# Ethernet.net
KiCad netlist of a schematic drawn in Altium Designer
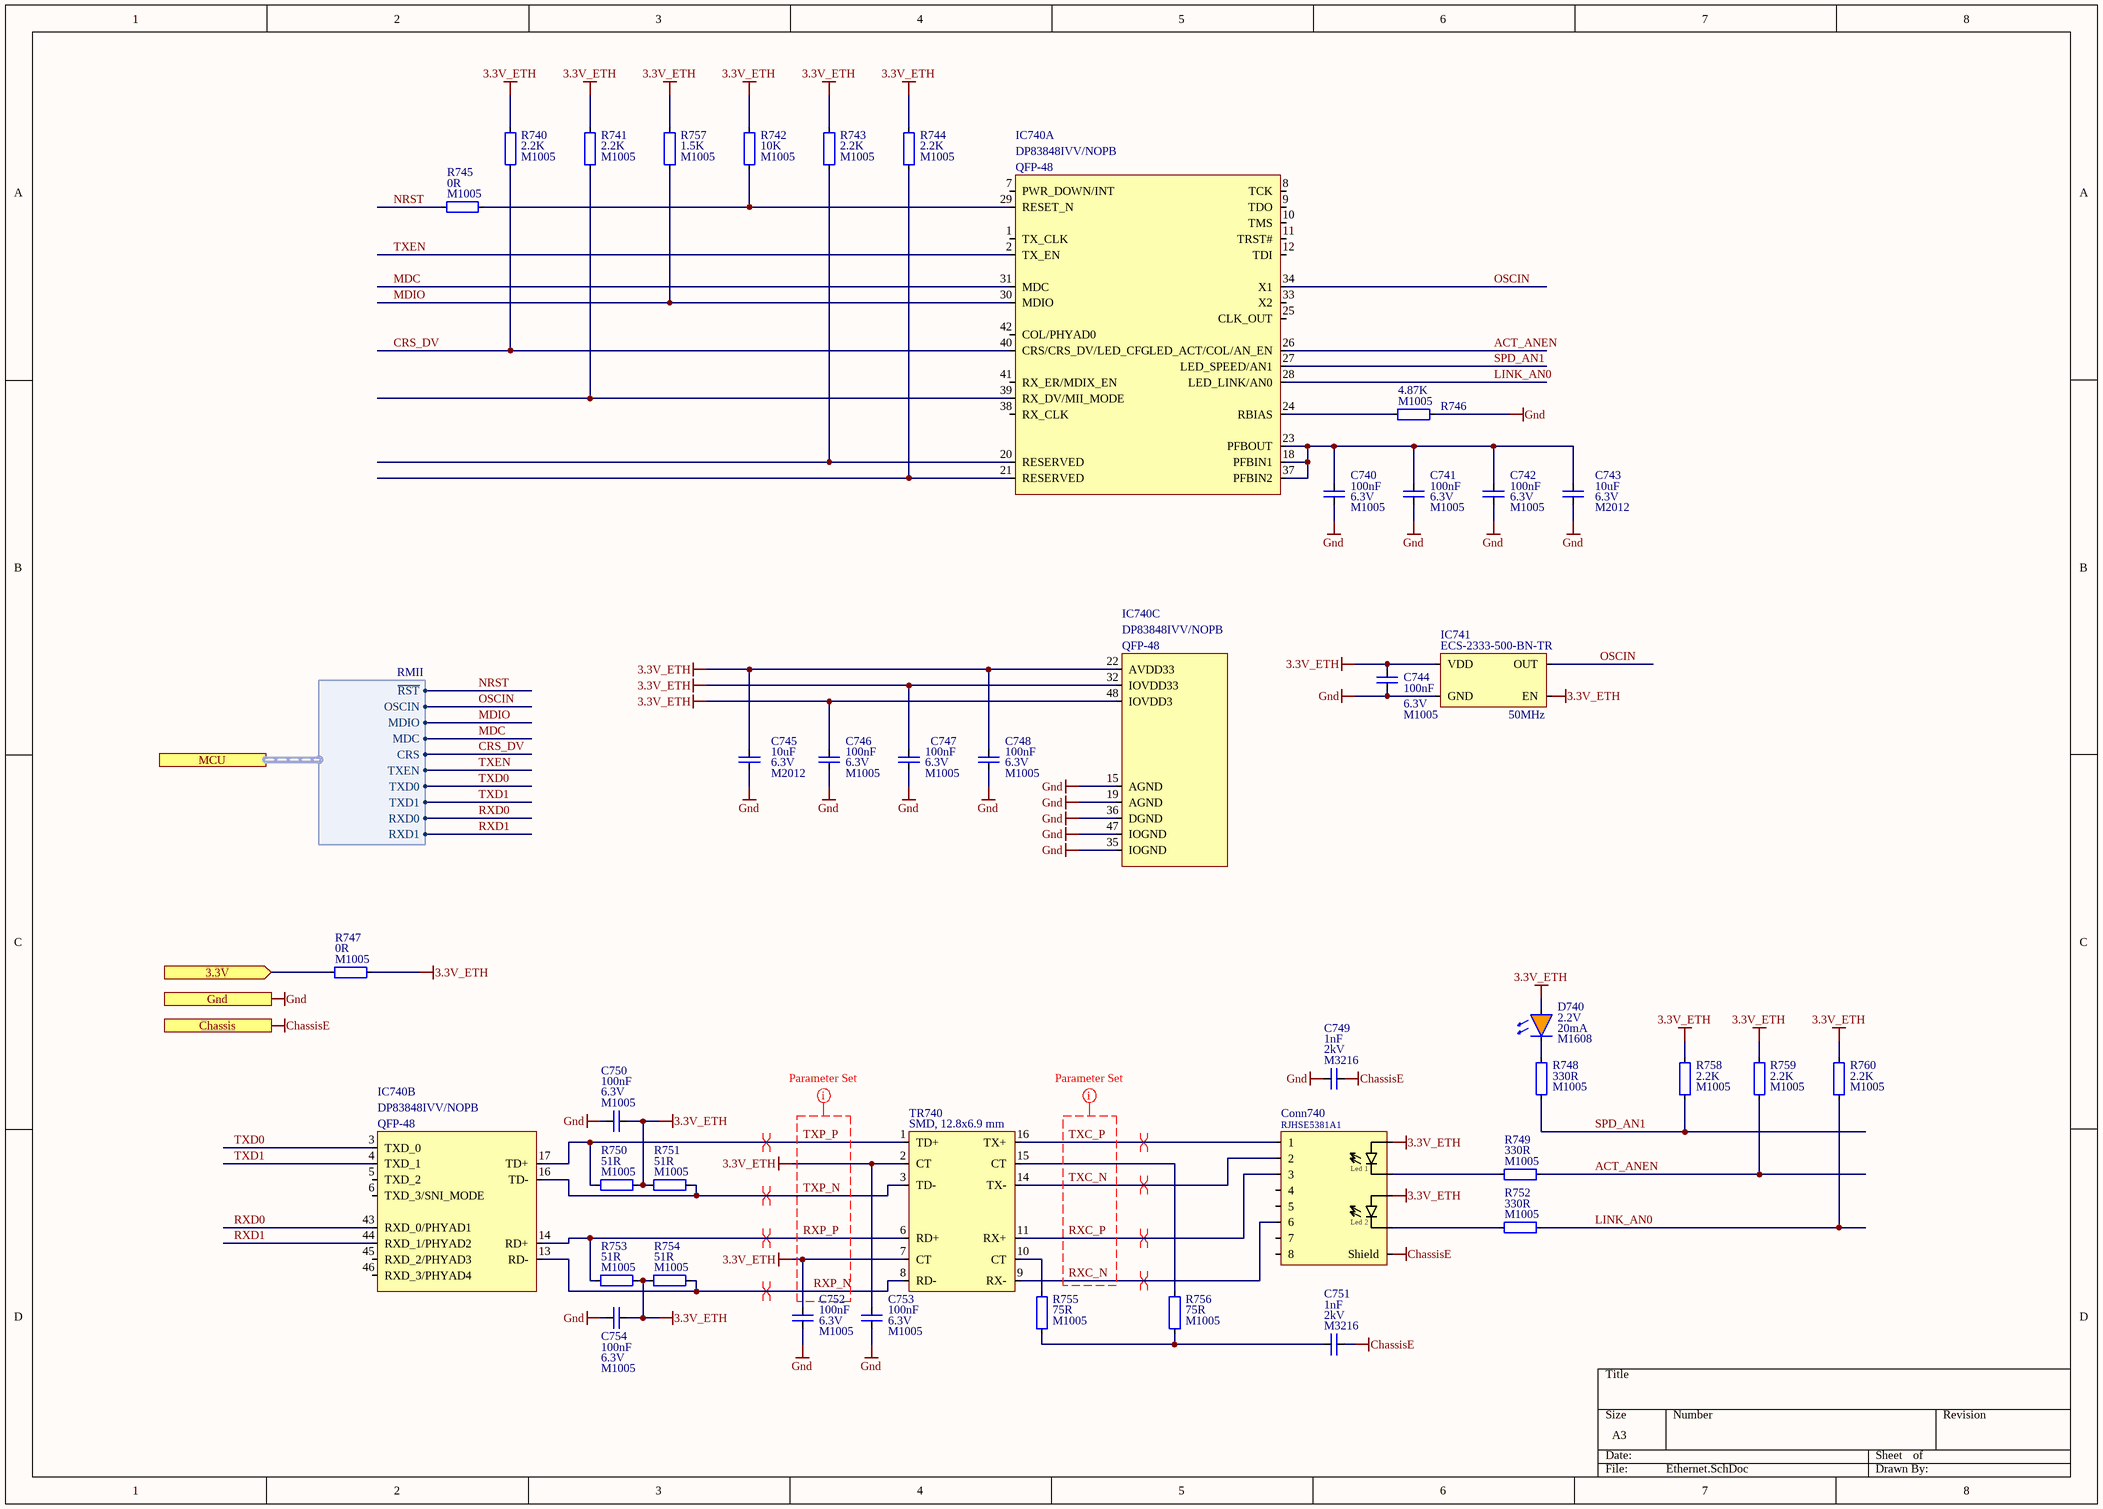
[diagram p0: Ethernet.SchDoc]

(export (version "E")
  (design (tool "Eeschema 10.0.6"))
  (components
    (comp (ref "C740")
      (value "100nF")
      (footprint "Capacitor_Ceramic_M1005_I0402")
      (description "Cap, Cer, 100nF, 6.3V, M1005")
      (fields
        (field (name "VOLTAGE") "6.3V")
        (field (name "MANUFACTURER PART NUMBER") "04026D104KAT4A")
        (field (name "MANUFACTURER") "Kyocera")
        (field (name "PACKAGE") "M1005")
      )
      (libsource (lib "Capacitor") (part "Capacitor_Ceramic"))
    )
    (comp (ref "C741")
      (value "100nF")
      (footprint "Capacitor_Ceramic_M1005_I0402")
      (description "Cap, Cer, 100nF, 6.3V, M1005")
      (fields
        (field (name "VOLTAGE") "6.3V")
        (field (name "MANUFACTURER PART NUMBER") "04026D104KAT4A")
        (field (name "MANUFACTURER") "Kyocera")
        (field (name "PACKAGE") "M1005")
      )
      (libsource (lib "Capacitor") (part "Capacitor_Ceramic"))
    )
    (comp (ref "C742")
      (value "100nF")
      (footprint "Capacitor_Ceramic_M1005_I0402")
      (description "Cap, Cer, 100nF, 6.3V, M1005")
      (fields
        (field (name "VOLTAGE") "6.3V")
        (field (name "MANUFACTURER PART NUMBER") "04026D104KAT4A")
        (field (name "MANUFACTURER") "Kyocera")
        (field (name "PACKAGE") "M1005")
      )
      (libsource (lib "Capacitor") (part "Capacitor_Ceramic"))
    )
    (comp (ref "C743")
      (value "10uF")
      (footprint "Capacitor_Ceramic_M2012_I0805")
      (description "Cap, Cer, 10uF, 6.3V, M2012")
      (fields
        (field (name "VOLTAGE") "6.3V")
        (field (name "MANUFACTURER PART NUMBER") "CL21A106MQFNNNE")
        (field (name "MANUFACTURER") "Samsung")
        (field (name "PACKAGE") "M2012")
      )
      (libsource (lib "Capacitor") (part "Capacitor_Ceramic"))
    )
    (comp (ref "C744")
      (value "100nF")
      (footprint "Capacitor_Ceramic_M1005_I0402")
      (description "Cap, Cer, 100nF, 6.3V, M1005")
      (fields
        (field (name "VOLTAGE") "6.3V")
        (field (name "MANUFACTURER PART NUMBER") "04026D104KAT4A")
        (field (name "MANUFACTURER") "Kyocera")
        (field (name "PACKAGE") "M1005")
      )
      (libsource (lib "Capacitor") (part "Capacitor_Ceramic"))
    )
    (comp (ref "C745")
      (value "10uF")
      (footprint "Capacitor_Ceramic_M2012_I0805")
      (description "Cap, Cer, 10uF, 6.3V, M2012")
      (fields
        (field (name "VOLTAGE") "6.3V")
        (field (name "MANUFACTURER PART NUMBER") "CL21A106MQFNNNE")
        (field (name "MANUFACTURER") "Samsung")
        (field (name "PACKAGE") "M2012")
      )
      (libsource (lib "Capacitor") (part "Capacitor_Ceramic"))
    )
    (comp (ref "C746")
      (value "100nF")
      (footprint "Capacitor_Ceramic_M1005_I0402")
      (description "Cap, Cer, 100nF, 6.3V, M1005")
      (fields
        (field (name "VOLTAGE") "6.3V")
        (field (name "MANUFACTURER PART NUMBER") "04026D104KAT4A")
        (field (name "MANUFACTURER") "Kyocera")
        (field (name "PACKAGE") "M1005")
      )
      (libsource (lib "Capacitor") (part "Capacitor_Ceramic"))
    )
    (comp (ref "C747")
      (value "100nF")
      (footprint "Capacitor_Ceramic_M1005_I0402")
      (description "Cap, Cer, 100nF, 6.3V, M1005")
      (fields
        (field (name "VOLTAGE") "6.3V")
        (field (name "MANUFACTURER PART NUMBER") "04026D104KAT4A")
        (field (name "MANUFACTURER") "Kyocera")
        (field (name "PACKAGE") "M1005")
      )
      (libsource (lib "Capacitor") (part "Capacitor_Ceramic"))
    )
    (comp (ref "C748")
      (value "100nF")
      (footprint "Capacitor_Ceramic_M1005_I0402")
      (description "Cap, Cer, 100nF, 6.3V, M1005")
      (fields
        (field (name "VOLTAGE") "6.3V")
        (field (name "MANUFACTURER PART NUMBER") "04026D104KAT4A")
        (field (name "MANUFACTURER") "Kyocera")
        (field (name "PACKAGE") "M1005")
      )
      (libsource (lib "Capacitor") (part "Capacitor_Ceramic"))
    )
    (comp (ref "C749")
      (value "1nF")
      (footprint "Capacitor_Ceramic_M3216_I1206")
      (description "Cap, Cer, 1nF, 2kV, M3216")
      (fields
        (field (name "VOLTAGE") "2kV")
        (field (name "MANUFACTURER PART NUMBER") "CC1206MKX7RDBB102")
        (field (name "MANUFACTURER") "Yageo")
        (field (name "PACKAGE") "M3216")
      )
      (libsource (lib "Capacitor") (part "Capacitor_Ceramic"))
    )
    (comp (ref "C750")
      (value "100nF")
      (footprint "Capacitor_Ceramic_M1005_I0402")
      (description "Cap, Cer, 100nF, 6.3V, M1005")
      (fields
        (field (name "VOLTAGE") "6.3V")
        (field (name "MANUFACTURER PART NUMBER") "04026D104KAT4A")
        (field (name "MANUFACTURER") "Kyocera")
        (field (name "PACKAGE") "M1005")
      )
      (libsource (lib "Capacitor") (part "Capacitor_Ceramic"))
    )
    (comp (ref "C751")
      (value "1nF")
      (footprint "Capacitor_Ceramic_M3216_I1206")
      (description "Cap, Cer, 1nF, 2kV, M3216")
      (fields
        (field (name "VOLTAGE") "2kV")
        (field (name "MANUFACTURER PART NUMBER") "CC1206MKX7RDBB102")
        (field (name "MANUFACTURER") "Yageo")
        (field (name "PACKAGE") "M3216")
      )
      (libsource (lib "Capacitor") (part "Capacitor_Ceramic"))
    )
    (comp (ref "C752")
      (value "100nF")
      (footprint "Capacitor_Ceramic_M1005_I0402")
      (description "Cap, Cer, 100nF, 6.3V, M1005")
      (fields
        (field (name "VOLTAGE") "6.3V")
        (field (name "MANUFACTURER PART NUMBER") "04026D104KAT4A")
        (field (name "MANUFACTURER") "Kyocera")
        (field (name "PACKAGE") "M1005")
      )
      (libsource (lib "Capacitor") (part "Capacitor_Ceramic"))
    )
    (comp (ref "C753")
      (value "100nF")
      (footprint "Capacitor_Ceramic_M1005_I0402")
      (description "Cap, Cer, 100nF, 6.3V, M1005")
      (fields
        (field (name "VOLTAGE") "6.3V")
        (field (name "MANUFACTURER PART NUMBER") "04026D104KAT4A")
        (field (name "MANUFACTURER") "Kyocera")
        (field (name "PACKAGE") "M1005")
      )
      (libsource (lib "Capacitor") (part "Capacitor_Ceramic"))
    )
    (comp (ref "C754")
      (value "100nF")
      (footprint "Capacitor_Ceramic_M1005_I0402")
      (description "Cap, Cer, 100nF, 6.3V, M1005")
      (fields
        (field (name "VOLTAGE") "6.3V")
        (field (name "MANUFACTURER PART NUMBER") "04026D104KAT4A")
        (field (name "MANUFACTURER") "Kyocera")
        (field (name "PACKAGE") "M1005")
      )
      (libsource (lib "Capacitor") (part "Capacitor_Ceramic"))
    )
    (comp (ref "Conn740")
      (value "RJ45 - Amphenol, RJHSE-x38x-A1")
      (footprint "RJ45 - Amphenol, RJHSE-x38x-A1")
      (description "Conn, RJ45, 2 Leds, Shielded, Side Entry")
      (fields
        (field (name "MANUFACTURER") "Amphenol")
        (field (name "MANUFACTURER PART NUMBER") "RJHSE5381A1")
      )
      (libsource (lib "Connector - Registered Jack") (part "RJ45 - Amphenol, RJHSE-x38x-A1"))
    )
    (comp (ref "D740")
      (value "Diode_Led")
      (footprint "Diode_Smd_M1608_I0603_Orange1")
      (description "Diode, Led, Orange, 2.2V, 20mA, M1608")
      (fields
        (field (name "MANUFACTURER PART NUMBER") "SML-D12D1WT86")
        (field (name "MANUFACTURER") "Rohm")
        (field (name "CURRENT") "20mA")
        (field (name "VOLTAGE") "2.2V")
        (field (name "PACKAGE") "M1608")
      )
      (libsource (lib "Diode") (part "Diode_Led"))
    )
    (comp (ref "IC740")
      (value "Ethernet - Texas, DP83848xVV")
      (footprint "QFP-48, 7mm x 7mm, 0.5mm")
      (description "IC, Interface, Eth Phy, 10/100Mb, DP83848IVV")
      (fields
        (field (name "MANUFACTURER") "Texas")
        (field (name "MANUFACTURER PART NUMBER") "DP83848IVV/NOPB")
        (field (name "PACKAGE") "QFP-48")
      )
      (libsource (lib "IC - Interface") (part "Ethernet - Texas, DP83848xVV"))
    )
    (comp (ref "IC741")
      (value "Clock Oscillator - ECS, ECS-2325, ECS-2333")
      (footprint "Clock Oscillator - ECS, ECS-2325, ECS-2333")
      (description "IC, Oscillator, 50MHz")
      (fields
        (field (name "MANUFACTURER") "ECS")
        (field (name "FREQUENCY") "50MHz")
        (field (name "MANUFACTURER PART NUMBER") "ECS-2333-500-BN-TR")
      )
      (libsource (lib "IC - Clock, Timing, Oscillator") (part "Clock Oscillator - ECS, ECS-2325, ECS-2333"))
    )
    (comp (ref "R740")
      (value "2.2K")
      (footprint "Resistor_Smd_M1005_I0402")
      (description "Res, 2.2K, 1%, M1005")
      (fields
        (field (name "TOLERANCE") "1%")
        (field (name "MANUFACTURER") "Yageo")
        (field (name "PACKAGE") "M1005")
      )
      (libsource (lib "Resistor") (part "Resistor"))
    )
    (comp (ref "R741")
      (value "2.2K")
      (footprint "Resistor_Smd_M1005_I0402")
      (description "Res, 2.2K, 1%, M1005")
      (fields
        (field (name "TOLERANCE") "1%")
        (field (name "MANUFACTURER") "Yageo")
        (field (name "PACKAGE") "M1005")
      )
      (libsource (lib "Resistor") (part "Resistor"))
    )
    (comp (ref "R742")
      (value "10K")
      (footprint "Resistor_Smd_M1005_I0402")
      (description "Res, 10K, 1%, M1005")
      (fields
        (field (name "TOLERANCE") "1%")
        (field (name "MANUFACTURER") "Yageo")
        (field (name "PACKAGE") "M1005")
      )
      (libsource (lib "Resistor") (part "Resistor"))
    )
    (comp (ref "R743")
      (value "2.2K")
      (footprint "Resistor_Smd_M1005_I0402")
      (description "Res, 2.2K, 1%, M1005")
      (fields
        (field (name "TOLERANCE") "1%")
        (field (name "MANUFACTURER") "Yageo")
        (field (name "PACKAGE") "M1005")
      )
      (libsource (lib "Resistor") (part "Resistor"))
    )
    (comp (ref "R744")
      (value "2.2K")
      (footprint "Resistor_Smd_M1005_I0402")
      (description "Res, 2.2K, 1%, M1005")
      (fields
        (field (name "TOLERANCE") "1%")
        (field (name "MANUFACTURER") "Yageo")
        (field (name "PACKAGE") "M1005")
      )
      (libsource (lib "Resistor") (part "Resistor"))
    )
    (comp (ref "R745")
      (value "0R")
      (footprint "Resistor_Smd_M1005_I0402")
      (description "Res, 0R, M1005")
      (fields
        (field (name "MANUFACTURER") "Yageo")
        (field (name "MANUFACTURER PART NUMBER") "RC0402FR-070RL")
        (field (name "PACKAGE") "M1005")
      )
      (libsource (lib "Resistor") (part "Resistor"))
    )
    (comp (ref "R746")
      (value "4.87K")
      (footprint "Resistor_Smd_M1005_I0402")
      (description "Res, 4.87K, 1%, M1005")
      (fields
        (field (name "TOLERANCE") "1%")
        (field (name "MANUFACTURER") "Yageo")
        (field (name "PACKAGE") "M1005")
      )
      (libsource (lib "Resistor") (part "Resistor"))
    )
    (comp (ref "R747")
      (value "0R")
      (footprint "Resistor_Smd_M1005_I0402")
      (description "Res, 0R, M1005")
      (fields
        (field (name "MANUFACTURER") "Yageo")
        (field (name "MANUFACTURER PART NUMBER") "RC0402FR-070RL")
        (field (name "PACKAGE") "M1005")
      )
      (libsource (lib "Resistor") (part "Resistor"))
    )
    (comp (ref "R748")
      (value "330R")
      (footprint "Resistor_Smd_M1005_I0402")
      (description "Res, 330R, 1%, M1005")
      (fields
        (field (name "TOLERANCE") "1%")
        (field (name "MANUFACTURER") "Yageo")
        (field (name "PACKAGE") "M1005")
      )
      (libsource (lib "Resistor") (part "Resistor"))
    )
    (comp (ref "R749")
      (value "330R")
      (footprint "Resistor_Smd_M1005_I0402")
      (description "Res, 330R, 1%, M1005")
      (fields
        (field (name "TOLERANCE") "1%")
        (field (name "MANUFACTURER") "Yageo")
        (field (name "PACKAGE") "M1005")
      )
      (libsource (lib "Resistor") (part "Resistor"))
    )
    (comp (ref "R750")
      (value "51R")
      (footprint "Resistor_Smd_M1005_I0402")
      (description "Res, 51R, 1%, M1005")
      (fields
        (field (name "TOLERANCE") "1%")
        (field (name "MANUFACTURER") "Yageo")
        (field (name "PACKAGE") "M1005")
      )
      (libsource (lib "Resistor") (part "Resistor"))
    )
    (comp (ref "R751")
      (value "51R")
      (footprint "Resistor_Smd_M1005_I0402")
      (description "Res, 51R, 1%, M1005")
      (fields
        (field (name "TOLERANCE") "1%")
        (field (name "MANUFACTURER") "Yageo")
        (field (name "PACKAGE") "M1005")
      )
      (libsource (lib "Resistor") (part "Resistor"))
    )
    (comp (ref "R752")
      (value "330R")
      (footprint "Resistor_Smd_M1005_I0402")
      (description "Res, 330R, 1%, M1005")
      (fields
        (field (name "TOLERANCE") "1%")
        (field (name "MANUFACTURER") "Yageo")
        (field (name "PACKAGE") "M1005")
      )
      (libsource (lib "Resistor") (part "Resistor"))
    )
    (comp (ref "R753")
      (value "51R")
      (footprint "Resistor_Smd_M1005_I0402")
      (description "Res, 51R, 1%, M1005")
      (fields
        (field (name "TOLERANCE") "1%")
        (field (name "MANUFACTURER") "Yageo")
        (field (name "PACKAGE") "M1005")
      )
      (libsource (lib "Resistor") (part "Resistor"))
    )
    (comp (ref "R754")
      (value "51R")
      (footprint "Resistor_Smd_M1005_I0402")
      (description "Res, 51R, 1%, M1005")
      (fields
        (field (name "TOLERANCE") "1%")
        (field (name "MANUFACTURER") "Yageo")
        (field (name "PACKAGE") "M1005")
      )
      (libsource (lib "Resistor") (part "Resistor"))
    )
    (comp (ref "R755")
      (value "75R")
      (footprint "Resistor_Smd_M1005_I0402")
      (description "Res, 75R, 1%, M1005")
      (fields
        (field (name "TOLERANCE") "1%")
        (field (name "MANUFACTURER") "Yageo")
        (field (name "PACKAGE") "M1005")
      )
      (libsource (lib "Resistor") (part "Resistor"))
    )
    (comp (ref "R756")
      (value "75R")
      (footprint "Resistor_Smd_M1005_I0402")
      (description "Res, 75R, 1%, M1005")
      (fields
        (field (name "TOLERANCE") "1%")
        (field (name "MANUFACTURER") "Yageo")
        (field (name "PACKAGE") "M1005")
      )
      (libsource (lib "Resistor") (part "Resistor"))
    )
    (comp (ref "R757")
      (value "1.5K")
      (footprint "Resistor_Smd_M1005_I0402")
      (description "Res, 1.5K, 1%, M1005")
      (fields
        (field (name "TOLERANCE") "1%")
        (field (name "MANUFACTURER") "Yageo")
        (field (name "PACKAGE") "M1005")
      )
      (libsource (lib "Resistor") (part "Resistor"))
    )
    (comp (ref "R758")
      (value "2.2K")
      (footprint "Resistor_Smd_M1005_I0402")
      (description "Res, 2.2K, 1%, M1005")
      (fields
        (field (name "TOLERANCE") "1%")
        (field (name "MANUFACTURER") "Yageo")
        (field (name "PACKAGE") "M1005")
      )
      (libsource (lib "Resistor") (part "Resistor"))
    )
    (comp (ref "R759")
      (value "2.2K")
      (footprint "Resistor_Smd_M1005_I0402")
      (description "Res, 2.2K, 1%, M1005")
      (fields
        (field (name "TOLERANCE") "1%")
        (field (name "MANUFACTURER") "Yageo")
        (field (name "PACKAGE") "M1005")
      )
      (libsource (lib "Resistor") (part "Resistor"))
    )
    (comp (ref "R760")
      (value "2.2K")
      (footprint "Resistor_Smd_M1005_I0402")
      (description "Res, 2.2K, 1%, M1005")
      (fields
        (field (name "TOLERANCE") "1%")
        (field (name "MANUFACTURER") "Yageo")
        (field (name "PACKAGE") "M1005")
      )
      (libsource (lib "Resistor") (part "Resistor"))
    )
    (comp (ref "TR740")
      (value "Transformer, Pulse - Bourns, SM13126PEL")
      (footprint "Transformer, Pulse - Bourns, SM13126PEL")
      (description "Transformer, Eth, 100Mbps, SM13126PEL")
      (fields
        (field (name "MANUFACTURER PART NUMBER") "SM13126PEL")
        (field (name "MANUFACTURER") "Bourns")
        (field (name "PACKAGE") "SMD, 12.8x6.9 mm")
      )
      (libsource (lib "Transformer") (part "Transformer, Pulse - Bourns, SM13126PEL"))
    )
  )
  (nets
    (net (code "2") (name "/3.3V") (class "Default")
      (node (ref "R747") (pin "1") (pinfunction "1_1") (pintype "passive"))
    )
    (net (code "3") (name "/ACT_ANEN") (class "Default")
      (node (ref "IC740") (pin "26") (pinfunction "LED_ACT/COL/AN_EN_26") (pintype "passive"))
      (node (ref "R749") (pin "2") (pinfunction "2_2") (pintype "passive"))
      (node (ref "R759") (pin "2") (pinfunction "2_2") (pintype "passive"))
    )
    (net (code "4") (name "/CRS_DV") (class "Default")
      (node (ref "IC740") (pin "40") (pinfunction "CRS/CRS_DV/LED_CFG_40") (pintype "passive"))
      (node (ref "R740") (pin "2") (pinfunction "2_2") (pintype "passive"))
    )
    (net (code "5") (name "/LINK_AN0") (class "Default")
      (node (ref "IC740") (pin "28") (pinfunction "LED_LINK/AN0_28") (pintype "passive"))
      (node (ref "R752") (pin "2") (pinfunction "2_2") (pintype "passive"))
      (node (ref "R760") (pin "2") (pinfunction "2_2") (pintype "passive"))
    )
    (net (code "6") (name "/MDC") (class "Default")
      (node (ref "IC740") (pin "31") (pinfunction "MDC_31") (pintype "passive"))
    )
    (net (code "7") (name "/MDIO") (class "Default")
      (node (ref "IC740") (pin "30") (pinfunction "MDIO_30") (pintype "passive"))
      (node (ref "R757") (pin "2") (pinfunction "2_2") (pintype "passive"))
    )
    (net (code "8") (name "/NRST") (class "Default")
      (node (ref "R745") (pin "1") (pinfunction "1_1") (pintype "passive"))
    )
    (net (code "9") (name "/OSCIN") (class "Default")
      (node (ref "IC740") (pin "34") (pinfunction "X1_34") (pintype "passive"))
      (node (ref "IC741") (pin "OUT") (pinfunction "OUT_OUT") (pintype "passive"))
    )
    (net (code "10") (name "/RXC_N") (class "Default")
      (node (ref "Conn740") (pin "6") (pinfunction "6_6") (pintype "passive"))
      (node (ref "TR740") (pin "9") (pinfunction "RX-_9") (pintype "passive"))
    )
    (net (code "11") (name "/RXC_P") (class "Default")
      (node (ref "Conn740") (pin "3") (pinfunction "3_3") (pintype "passive"))
      (node (ref "TR740") (pin "11") (pinfunction "RX+_11") (pintype "passive"))
    )
    (net (code "12") (name "/RXD0") (class "Default")
      (node (ref "IC740") (pin "43") (pinfunction "RXD_0/PHYAD1_43") (pintype "passive"))
    )
    (net (code "13") (name "/RXD1") (class "Default")
      (node (ref "IC740") (pin "44") (pinfunction "RXD_1/PHYAD2_44") (pintype "passive"))
    )
    (net (code "14") (name "/RXP_N") (class "Default")
      (node (ref "IC740") (pin "13") (pinfunction "RD-_13") (pintype "passive"))
      (node (ref "R754") (pin "2") (pinfunction "2_2") (pintype "passive"))
      (node (ref "TR740") (pin "8") (pinfunction "RD-_8") (pintype "passive"))
    )
    (net (code "15") (name "/RXP_P") (class "Default")
      (node (ref "IC740") (pin "14") (pinfunction "RD+_14") (pintype "passive"))
      (node (ref "R753") (pin "1") (pinfunction "1_1") (pintype "passive"))
      (node (ref "TR740") (pin "6") (pinfunction "RD+_6") (pintype "passive"))
    )
    (net (code "16") (name "/SPD_AN1") (class "Default")
      (node (ref "IC740") (pin "27") (pinfunction "LED_SPEED/AN1_27") (pintype "passive"))
      (node (ref "R748") (pin "2") (pinfunction "2_2") (pintype "passive"))
      (node (ref "R758") (pin "2") (pinfunction "2_2") (pintype "passive"))
    )
    (net (code "17") (name "/TXC_N") (class "Default")
      (node (ref "Conn740") (pin "2") (pinfunction "2_2") (pintype "passive"))
      (node (ref "TR740") (pin "14") (pinfunction "TX-_14") (pintype "passive"))
    )
    (net (code "18") (name "/TXC_P") (class "Default")
      (node (ref "Conn740") (pin "1") (pinfunction "1_1") (pintype "passive"))
      (node (ref "TR740") (pin "16") (pinfunction "TX+_16") (pintype "passive"))
    )
    (net (code "19") (name "/TXD0") (class "Default")
      (node (ref "IC740") (pin "3") (pinfunction "TXD_0_3") (pintype "passive"))
    )
    (net (code "20") (name "/TXD1") (class "Default")
      (node (ref "IC740") (pin "4") (pinfunction "TXD_1_4") (pintype "passive"))
    )
    (net (code "21") (name "/TXEN") (class "Default")
      (node (ref "IC740") (pin "2") (pinfunction "TX_EN_2") (pintype "passive"))
    )
    (net (code "22") (name "/TXP_N") (class "Default")
      (node (ref "IC740") (pin "16") (pinfunction "TD-_16") (pintype "passive"))
      (node (ref "R751") (pin "2") (pinfunction "2_2") (pintype "passive"))
      (node (ref "TR740") (pin "3") (pinfunction "TD-_3") (pintype "passive"))
    )
    (net (code "23") (name "/TXP_P") (class "Default")
      (node (ref "IC740") (pin "17") (pinfunction "TD+_17") (pintype "passive"))
      (node (ref "R750") (pin "1") (pinfunction "1_1") (pintype "passive"))
      (node (ref "TR740") (pin "1") (pinfunction "TD+_1") (pintype "passive"))
    )
    (net (code "25") (name "3.3V_ETH") (class "Default")
      (node (ref "C744") (pin "1") (pinfunction "1_1") (pintype "passive"))
      (node (ref "C745") (pin "1") (pinfunction "1_1") (pintype "passive"))
      (node (ref "C746") (pin "1") (pinfunction "1_1") (pintype "passive"))
      (node (ref "C747") (pin "1") (pinfunction "1_1") (pintype "passive"))
      (node (ref "C748") (pin "1") (pinfunction "1_1") (pintype "passive"))
      (node (ref "C750") (pin "2") (pinfunction "2_2") (pintype "passive"))
      (node (ref "C752") (pin "1") (pinfunction "1_1") (pintype "passive"))
      (node (ref "C753") (pin "1") (pinfunction "1_1") (pintype "passive"))
      (node (ref "C754") (pin "2") (pinfunction "2_2") (pintype "passive"))
      (node (ref "Conn740") (pin "L1-A") (pinfunction "L1-A_L1-A") (pintype "passive"))
      (node (ref "Conn740") (pin "L2-A") (pinfunction "L2-A_L2-A") (pintype "passive"))
      (node (ref "D740") (pin "A") (pinfunction "A_A") (pintype "passive"))
      (node (ref "IC740") (pin "22") (pinfunction "AVDD33_22") (pintype "passive"))
      (node (ref "IC740") (pin "32") (pinfunction "IOVDD33_32") (pintype "passive"))
      (node (ref "IC740") (pin "48") (pinfunction "IOVDD3_48") (pintype "passive"))
      (node (ref "IC741") (pin "EN") (pinfunction "EN_EN") (pintype "passive"))
      (node (ref "IC741") (pin "VDD") (pinfunction "VDD_VDD") (pintype "passive"))
      (node (ref "R740") (pin "1") (pinfunction "1_1") (pintype "passive"))
      (node (ref "R741") (pin "1") (pinfunction "1_1") (pintype "passive"))
      (node (ref "R742") (pin "1") (pinfunction "1_1") (pintype "passive"))
      (node (ref "R743") (pin "1") (pinfunction "1_1") (pintype "passive"))
      (node (ref "R744") (pin "1") (pinfunction "1_1") (pintype "passive"))
      (node (ref "R747") (pin "2") (pinfunction "2_2") (pintype "passive"))
      (node (ref "R750") (pin "2") (pinfunction "2_2") (pintype "passive"))
      (node (ref "R751") (pin "1") (pinfunction "1_1") (pintype "passive"))
      (node (ref "R753") (pin "2") (pinfunction "2_2") (pintype "passive"))
      (node (ref "R754") (pin "1") (pinfunction "1_1") (pintype "passive"))
      (node (ref "R757") (pin "1") (pinfunction "1_1") (pintype "passive"))
      (node (ref "R758") (pin "1") (pinfunction "1_1") (pintype "passive"))
      (node (ref "R759") (pin "1") (pinfunction "1_1") (pintype "passive"))
      (node (ref "R760") (pin "1") (pinfunction "1_1") (pintype "passive"))
      (node (ref "TR740") (pin "2") (pinfunction "CT_2") (pintype "passive"))
      (node (ref "TR740") (pin "7") (pinfunction "CT_7") (pintype "passive"))
    )
    (net (code "26") (name "ChassisE") (class "Default")
      (node (ref "C749") (pin "2") (pinfunction "2_2") (pintype "passive"))
      (node (ref "C751") (pin "2") (pinfunction "2_2") (pintype "passive"))
      (node (ref "Conn740") (pin "Shield") (pinfunction "Shield_Shield") (pintype "passive"))
    )
    (net (code "27") (name "Gnd") (class "Default")
      (node (ref "C740") (pin "2") (pinfunction "2_2") (pintype "passive"))
      (node (ref "C741") (pin "2") (pinfunction "2_2") (pintype "passive"))
      (node (ref "C742") (pin "2") (pinfunction "2_2") (pintype "passive"))
      (node (ref "C743") (pin "2") (pinfunction "2_2") (pintype "passive"))
      (node (ref "C744") (pin "2") (pinfunction "2_2") (pintype "passive"))
      (node (ref "C745") (pin "2") (pinfunction "2_2") (pintype "passive"))
      (node (ref "C746") (pin "2") (pinfunction "2_2") (pintype "passive"))
      (node (ref "C747") (pin "2") (pinfunction "2_2") (pintype "passive"))
      (node (ref "C748") (pin "2") (pinfunction "2_2") (pintype "passive"))
      (node (ref "C749") (pin "1") (pinfunction "1_1") (pintype "passive"))
      (node (ref "C750") (pin "1") (pinfunction "1_1") (pintype "passive"))
      (node (ref "C752") (pin "2") (pinfunction "2_2") (pintype "passive"))
      (node (ref "C753") (pin "2") (pinfunction "2_2") (pintype "passive"))
      (node (ref "C754") (pin "1") (pinfunction "1_1") (pintype "passive"))
      (node (ref "IC740") (pin "15") (pinfunction "AGND_15") (pintype "passive"))
      (node (ref "IC740") (pin "19") (pinfunction "AGND_19") (pintype "passive"))
      (node (ref "IC740") (pin "35") (pinfunction "IOGND_35") (pintype "passive"))
      (node (ref "IC740") (pin "36") (pinfunction "DGND_36") (pintype "passive"))
      (node (ref "IC740") (pin "47") (pinfunction "IOGND_47") (pintype "passive"))
      (node (ref "IC741") (pin "GND") (pinfunction "GND_GND") (pintype "passive"))
      (node (ref "R746") (pin "2") (pinfunction "2_2") (pintype "passive"))
    )
    (net (code "28") (name "Net-(C751-Pad1)") (class "Default")
      (node (ref "C751") (pin "1") (pinfunction "1_1") (pintype "passive"))
      (node (ref "R755") (pin "2") (pinfunction "2_2") (pintype "passive"))
      (node (ref "R756") (pin "2") (pinfunction "2_2") (pintype "passive"))
    )
    (net (code "29") (name "Net-(Conn740-PadL1-C)") (class "Default")
      (node (ref "Conn740") (pin "L1-C") (pinfunction "L1-C_L1-C") (pintype "passive"))
      (node (ref "R749") (pin "1") (pinfunction "1_1") (pintype "passive"))
    )
    (net (code "30") (name "Net-(Conn740-PadL2-C)") (class "Default")
      (node (ref "Conn740") (pin "L2-C") (pinfunction "L2-C_L2-C") (pintype "passive"))
      (node (ref "R752") (pin "1") (pinfunction "1_1") (pintype "passive"))
    )
    (net (code "31") (name "Net-(D740-PadC)") (class "Default")
      (node (ref "D740") (pin "C") (pinfunction "C_C") (pintype "passive"))
      (node (ref "R748") (pin "1") (pinfunction "1_1") (pintype "passive"))
    )
    (net (code "32") (name "Net-(IC740A-PFBIN1)") (class "Default")
      (node (ref "C740") (pin "1") (pinfunction "1_1") (pintype "passive"))
      (node (ref "C741") (pin "1") (pinfunction "1_1") (pintype "passive"))
      (node (ref "C742") (pin "1") (pinfunction "1_1") (pintype "passive"))
      (node (ref "C743") (pin "1") (pinfunction "1_1") (pintype "passive"))
      (node (ref "IC740") (pin "18") (pinfunction "PFBIN1_18") (pintype "passive"))
      (node (ref "IC740") (pin "23") (pinfunction "PFBOUT_23") (pintype "passive"))
      (node (ref "IC740") (pin "37") (pinfunction "PFBIN2_37") (pintype "passive"))
    )
    (net (code "33") (name "Net-(IC740A-RBIAS)") (class "Default")
      (node (ref "IC740") (pin "24") (pinfunction "RBIAS_24") (pintype "passive"))
      (node (ref "R746") (pin "1") (pinfunction "1_1") (pintype "passive"))
    )
    (net (code "34") (name "Net-(IC740A-RESERVED-Pad20)") (class "Default")
      (node (ref "IC740") (pin "20") (pinfunction "RESERVED_20") (pintype "passive"))
      (node (ref "R743") (pin "2") (pinfunction "2_2") (pintype "passive"))
    )
    (net (code "35") (name "Net-(IC740A-RESERVED-Pad21)") (class "Default")
      (node (ref "IC740") (pin "21") (pinfunction "RESERVED_21") (pintype "passive"))
      (node (ref "R744") (pin "2") (pinfunction "2_2") (pintype "passive"))
    )
    (net (code "36") (name "Net-(IC740A-RESET_N)") (class "Default")
      (node (ref "IC740") (pin "29") (pinfunction "RESET_N_29") (pintype "passive"))
      (node (ref "R742") (pin "2") (pinfunction "2_2") (pintype "passive"))
      (node (ref "R745") (pin "2") (pinfunction "2_2") (pintype "passive"))
    )
    (net (code "37") (name "Net-(IC740A-RX_DV{slash}MII_MODE)") (class "Default")
      (node (ref "IC740") (pin "39") (pinfunction "RX_DV/MII_MODE_39") (pintype "passive"))
      (node (ref "R741") (pin "2") (pinfunction "2_2") (pintype "passive"))
    )
    (net (code "38") (name "Net-(R755-Pad1)") (class "Default")
      (node (ref "R755") (pin "1") (pinfunction "1_1") (pintype "passive"))
      (node (ref "TR740") (pin "10") (pinfunction "CT_10") (pintype "passive"))
    )
    (net (code "39") (name "Net-(R756-Pad1)") (class "Default")
      (node (ref "R756") (pin "1") (pinfunction "1_1") (pintype "passive"))
      (node (ref "TR740") (pin "15") (pinfunction "CT_15") (pintype "passive"))
    )
    (net (code "40") (name "unconnected-(Conn740-Pad4)") (class "Default")
      (node (ref "Conn740") (pin "4") (pinfunction "4_4") (pintype "passive"))
    )
    (net (code "41") (name "unconnected-(Conn740-Pad5)") (class "Default")
      (node (ref "Conn740") (pin "5") (pinfunction "5_5") (pintype "passive"))
    )
    (net (code "42") (name "unconnected-(Conn740-Pad7)") (class "Default")
      (node (ref "Conn740") (pin "7") (pinfunction "7_7") (pintype "passive"))
    )
    (net (code "43") (name "unconnected-(Conn740-Pad8)") (class "Default")
      (node (ref "Conn740") (pin "8") (pinfunction "8_8") (pintype "passive"))
    )
    (net (code "44") (name "unconnected-(IC740A-CLK_OUT-Pad25)") (class "Default")
      (node (ref "IC740") (pin "25") (pinfunction "CLK_OUT_25") (pintype "passive"))
    )
    (net (code "45") (name "unconnected-(IC740A-COL{slash}PHYAD0-Pad42)") (class "Default")
      (node (ref "IC740") (pin "42") (pinfunction "COL/PHYAD0_42") (pintype "passive"))
    )
    (net (code "46") (name "unconnected-(IC740A-PWR_DOWN{slash}INT-Pad7)") (class "Default")
      (node (ref "IC740") (pin "7") (pinfunction "PWR_DOWN/INT_7") (pintype "passive"))
    )
    (net (code "47") (name "unconnected-(IC740A-RX_CLK-Pad38)") (class "Default")
      (node (ref "IC740") (pin "38") (pinfunction "RX_CLK_38") (pintype "passive"))
    )
    (net (code "48") (name "unconnected-(IC740A-RX_ER{slash}MDIX_EN-Pad41)") (class "Default")
      (node (ref "IC740") (pin "41") (pinfunction "RX_ER/MDIX_EN_41") (pintype "passive"))
    )
    (net (code "49") (name "unconnected-(IC740A-TCK-Pad8)") (class "Default")
      (node (ref "IC740") (pin "8") (pinfunction "TCK_8") (pintype "passive"))
    )
    (net (code "50") (name "unconnected-(IC740A-TDI-Pad12)") (class "Default")
      (node (ref "IC740") (pin "12") (pinfunction "TDI_12") (pintype "passive"))
    )
    (net (code "51") (name "unconnected-(IC740A-TDO-Pad9)") (class "Default")
      (node (ref "IC740") (pin "9") (pinfunction "TDO_9") (pintype "passive"))
    )
    (net (code "52") (name "unconnected-(IC740A-TMS-Pad10)") (class "Default")
      (node (ref "IC740") (pin "10") (pinfunction "TMS_10") (pintype "passive"))
    )
    (net (code "53") (name "unconnected-(IC740A-TRST#-Pad11)") (class "Default")
      (node (ref "IC740") (pin "11") (pinfunction "TRST#_11") (pintype "passive"))
    )
    (net (code "54") (name "unconnected-(IC740A-TX_CLK-Pad1)") (class "Default")
      (node (ref "IC740") (pin "1") (pinfunction "TX_CLK_1") (pintype "passive"))
    )
    (net (code "55") (name "unconnected-(IC740A-X2-Pad33)") (class "Default")
      (node (ref "IC740") (pin "33") (pinfunction "X2_33") (pintype "passive"))
    )
    (net (code "56") (name "unconnected-(IC740B-RXD_2{slash}PHYAD3-Pad45)") (class "Default")
      (node (ref "IC740") (pin "45") (pinfunction "RXD_2/PHYAD3_45") (pintype "passive"))
    )
    (net (code "57") (name "unconnected-(IC740B-RXD_3{slash}PHYAD4-Pad46)") (class "Default")
      (node (ref "IC740") (pin "46") (pinfunction "RXD_3/PHYAD4_46") (pintype "passive"))
    )
    (net (code "58") (name "unconnected-(IC740B-TXD_2-Pad5)") (class "Default")
      (node (ref "IC740") (pin "5") (pinfunction "TXD_2_5") (pintype "passive"))
    )
    (net (code "59") (name "unconnected-(IC740B-TXD_3{slash}SNI_MODE-Pad6)") (class "Default")
      (node (ref "IC740") (pin "6") (pinfunction "TXD_3/SNI_MODE_6") (pintype "passive"))
    )
  )
)
